# AC_Power_Management.net
KiCad netlist of a schematic drawn in Altium Designer
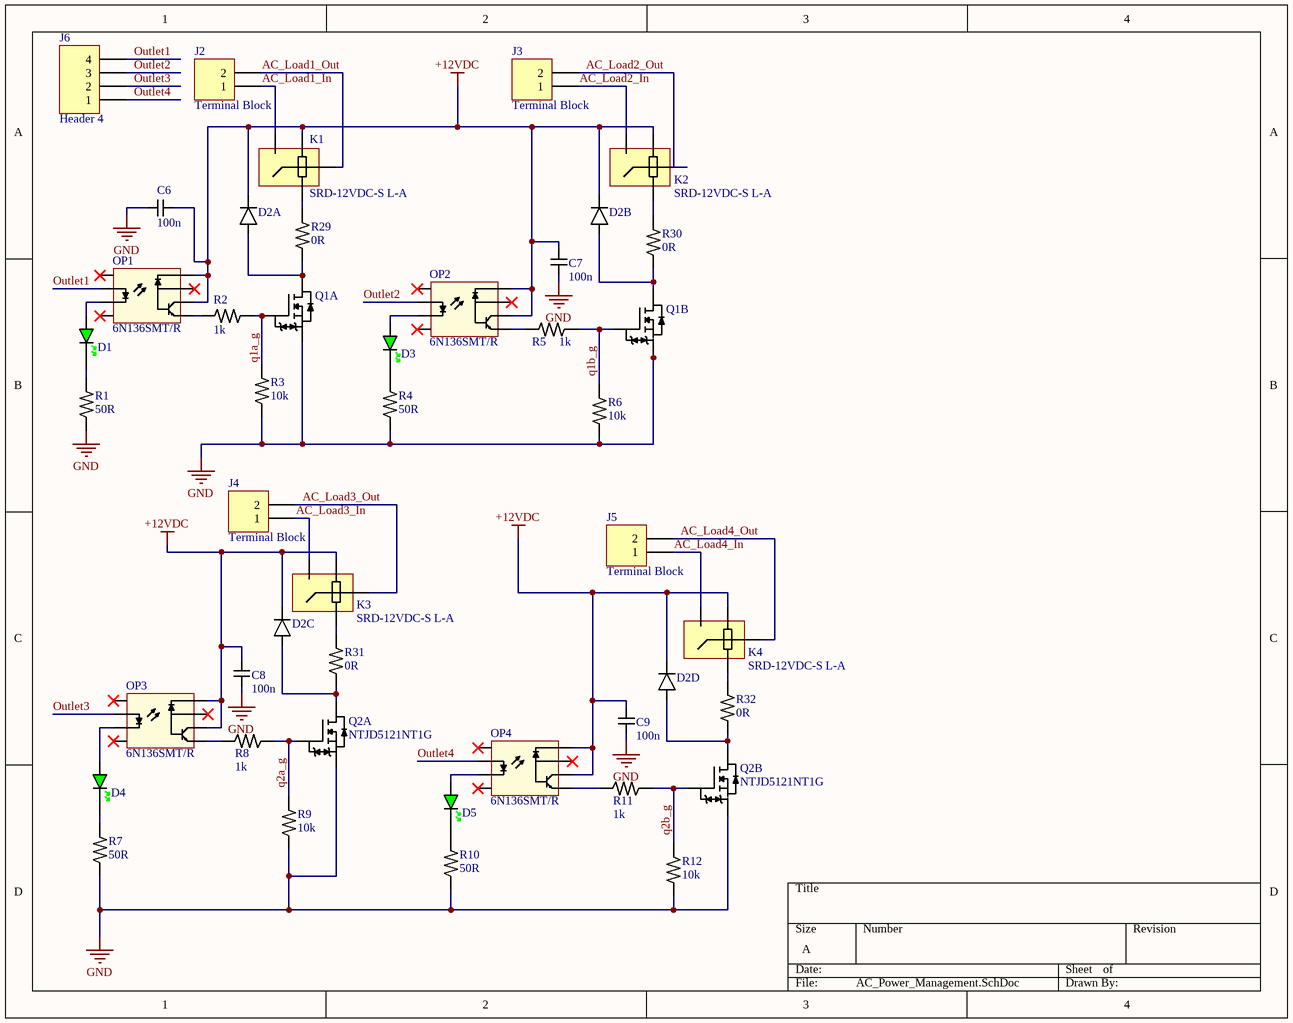
[diagram p0: AC_Power_Management.SchDoc]

(export (version "E")
  (design (tool "Eeschema 10.0.6"))
  (components
    (comp (ref "C6")
      (value "100n")
      (footprint "CAP_0402")
      (libsource (lib "PEAK_SCHEM_LIB") (part "CAP_0402"))
    )
    (comp (ref "C7")
      (value "100n")
      (footprint "CAP_0402")
      (libsource (lib "PEAK_SCHEM_LIB") (part "CAP_0402"))
    )
    (comp (ref "C8")
      (value "100n")
      (footprint "CAP_0402")
      (libsource (lib "PEAK_SCHEM_LIB") (part "CAP_0402"))
    )
    (comp (ref "C9")
      (value "100n")
      (footprint "CAP_0402")
      (libsource (lib "PEAK_SCHEM_LIB") (part "CAP_0402"))
    )
    (comp (ref "D1")
      (value "GREEN")
      (footprint "LED_0805_GREEN")
      (description "LED 0805 GREEN SMD")
      (libsource (lib "PEAK_SCHEM_LIB") (part "LED_0805_GREEN"))
    )
    (comp (ref "D2")
      (value "BAT54CDW-7-F")
      (footprint "SOT-363")
      (description "2 Pairs of Common Cathode Diodes in SOT363 Package BAT54CDW-7-F")
      (libsource (lib "PEAK_SCHEM_LIB") (part "BAT54CDW-7-F"))
    )
    (comp (ref "D3")
      (value "GREEN")
      (footprint "LED_0805_GREEN")
      (description "LED 0805 GREEN SMD")
      (libsource (lib "PEAK_SCHEM_LIB") (part "LED_0805_GREEN"))
    )
    (comp (ref "D4")
      (value "GREEN")
      (footprint "LED_0805_GREEN")
      (description "LED 0805 GREEN SMD")
      (libsource (lib "PEAK_SCHEM_LIB") (part "LED_0805_GREEN"))
    )
    (comp (ref "D5")
      (value "GREEN")
      (footprint "LED_0805_GREEN")
      (description "LED 0805 GREEN SMD")
      (libsource (lib "PEAK_SCHEM_LIB") (part "LED_0805_GREEN"))
    )
    (comp (ref "J2")
      (value "Terminal Block")
      (footprint "25-E400-02")
      (description "Header, 2-Pin")
      (fields (field (name "PUBLISHER") "Altium Limited"))
      (libsource (lib "Miscellaneous Connectors") (part "Header 2"))
    )
    (comp (ref "J3")
      (value "Terminal Block")
      (footprint "25-E400-02")
      (description "Header, 2-Pin")
      (fields (field (name "PUBLISHER") "Altium Limited"))
      (libsource (lib "Miscellaneous Connectors") (part "Header 2"))
    )
    (comp (ref "J4")
      (value "Terminal Block")
      (footprint "25-E400-02")
      (description "Header, 2-Pin")
      (fields (field (name "PUBLISHER") "Altium Limited"))
      (libsource (lib "Miscellaneous Connectors") (part "Header 2"))
    )
    (comp (ref "J5")
      (value "Terminal Block")
      (footprint "25-E400-02")
      (description "Header, 2-Pin")
      (fields (field (name "PUBLISHER") "Altium Limited"))
      (libsource (lib "Miscellaneous Connectors") (part "Header 2"))
    )
    (comp (ref "J6")
      (value "Header 4")
      (footprint "HDR1X4")
      (description "Header, 4-Pin")
      (fields (field (name "PUBLISHER") "Altium Limited"))
      (libsource (lib "Miscellaneous Connectors") (part "Header 4"))
    )
    (comp (ref "K1")
      (value "SRD-12VDC-S L-A")
      (footprint "SRD-12VDC-S L")
      (libsource (lib "PEAK_SCHEM_LIB") (part "SRD-12VDC-S L-A"))
    )
    (comp (ref "K2")
      (value "SRD-12VDC-S L-A")
      (footprint "SRD-12VDC-S L")
      (libsource (lib "PEAK_SCHEM_LIB") (part "SRD-12VDC-S L-A"))
    )
    (comp (ref "K3")
      (value "SRD-12VDC-S L-A")
      (footprint "SRD-12VDC-S L")
      (libsource (lib "PEAK_SCHEM_LIB") (part "SRD-12VDC-S L-A"))
    )
    (comp (ref "K4")
      (value "SRD-12VDC-S L-A")
      (footprint "SRD-12VDC-S L")
      (libsource (lib "PEAK_SCHEM_LIB") (part "SRD-12VDC-S L-A"))
    )
    (comp (ref "OP1")
      (value "6N136SMT/R")
      (footprint "SOP-8-2.54mm")
      (description "Optocouplers SMD-8 RoHS. SOP-8-2.54mm Package")
      (libsource (lib "PEAK_SCHEM_LIB") (part "6N136SMT/R"))
    )
    (comp (ref "OP2")
      (value "6N136SMT/R")
      (footprint "SOP-8-2.54mm")
      (description "Optocouplers SMD-8 RoHS. SOP-8-2.54mm Package")
      (libsource (lib "PEAK_SCHEM_LIB") (part "6N136SMT/R"))
    )
    (comp (ref "OP3")
      (value "6N136SMT/R")
      (footprint "SOP-8-2.54mm")
      (description "Optocouplers SMD-8 RoHS. SOP-8-2.54mm Package")
      (libsource (lib "PEAK_SCHEM_LIB") (part "6N136SMT/R"))
    )
    (comp (ref "OP4")
      (value "6N136SMT/R")
      (footprint "SOP-8-2.54mm")
      (description "Optocouplers SMD-8 RoHS. SOP-8-2.54mm Package")
      (libsource (lib "PEAK_SCHEM_LIB") (part "6N136SMT/R"))
    )
    (comp (ref "Q1")
      (value "NTJD5121NT1G")
      (footprint "SOT-363")
      (description "2 NMOSFETs SOT-363")
      (libsource (lib "PEAK_SCHEM_LIB") (part "NTJD5121NT1G"))
    )
    (comp (ref "Q2")
      (value "NTJD5121NT1G")
      (footprint "SOT-363")
      (description "2 NMOSFETs SOT-363")
      (libsource (lib "PEAK_SCHEM_LIB") (part "NTJD5121NT1G"))
    )
    (comp (ref "R1")
      (value "50R")
      (footprint "RES_0402")
      (description "Resistor SMD 0402 (0.0625W)")
      (libsource (lib "PEAK_SCHEM_LIB") (part "RES_0402"))
    )
    (comp (ref "R2")
      (value "1k")
      (footprint "RES_0402")
      (description "Resistor SMD 0402 (0.0625W)")
      (libsource (lib "PEAK_SCHEM_LIB") (part "RES_0402"))
    )
    (comp (ref "R3")
      (value "10k")
      (footprint "RES_0402")
      (description "Resistor SMD 0402 (0.0625W)")
      (libsource (lib "PEAK_SCHEM_LIB") (part "RES_0402"))
    )
    (comp (ref "R4")
      (value "50R")
      (footprint "RES_0402")
      (description "Resistor SMD 0402 (0.0625W)")
      (libsource (lib "PEAK_SCHEM_LIB") (part "RES_0402"))
    )
    (comp (ref "R5")
      (value "1k")
      (footprint "RES_0402")
      (description "Resistor SMD 0402 (0.0625W)")
      (libsource (lib "PEAK_SCHEM_LIB") (part "RES_0402"))
    )
    (comp (ref "R6")
      (value "10k")
      (footprint "RES_0402")
      (description "Resistor SMD 0402 (0.0625W)")
      (libsource (lib "PEAK_SCHEM_LIB") (part "RES_0402"))
    )
    (comp (ref "R7")
      (value "50R")
      (footprint "RES_0402")
      (description "Resistor SMD 0402 (0.0625W)")
      (libsource (lib "PEAK_SCHEM_LIB") (part "RES_0402"))
    )
    (comp (ref "R8")
      (value "1k")
      (footprint "RES_0402")
      (description "Resistor SMD 0402 (0.0625W)")
      (libsource (lib "PEAK_SCHEM_LIB") (part "RES_0402"))
    )
    (comp (ref "R9")
      (value "10k")
      (footprint "RES_0402")
      (description "Resistor SMD 0402 (0.0625W)")
      (libsource (lib "PEAK_SCHEM_LIB") (part "RES_0402"))
    )
    (comp (ref "R10")
      (value "50R")
      (footprint "RES_0402")
      (description "Resistor SMD 0402 (0.0625W)")
      (libsource (lib "PEAK_SCHEM_LIB") (part "RES_0402"))
    )
    (comp (ref "R11")
      (value "1k")
      (footprint "RES_0402")
      (description "Resistor SMD 0402 (0.0625W)")
      (libsource (lib "PEAK_SCHEM_LIB") (part "RES_0402"))
    )
    (comp (ref "R12")
      (value "10k")
      (footprint "RES_0402")
      (description "Resistor SMD 0402 (0.0625W)")
      (libsource (lib "PEAK_SCHEM_LIB") (part "RES_0402"))
    )
    (comp (ref "R29")
      (value "0R")
      (footprint "RES_0402")
      (description "Resistor SMD 0402 (0.0625W)")
      (libsource (lib "PEAK_SCHEM_LIB") (part "RES_0402"))
    )
    (comp (ref "R30")
      (value "0R")
      (footprint "RES_0402")
      (description "Resistor SMD 0402 (0.0625W)")
      (libsource (lib "PEAK_SCHEM_LIB") (part "RES_0402"))
    )
    (comp (ref "R31")
      (value "0R")
      (footprint "RES_0402")
      (description "Resistor SMD 0402 (0.0625W)")
      (libsource (lib "PEAK_SCHEM_LIB") (part "RES_0402"))
    )
    (comp (ref "R32")
      (value "0R")
      (footprint "RES_0402")
      (description "Resistor SMD 0402 (0.0625W)")
      (libsource (lib "PEAK_SCHEM_LIB") (part "RES_0402"))
    )
  )
  (nets
    (net (code "1") (name "+12VDC") (class "Default")
      (node (ref "C6") (pin "1") (pinfunction "1_1") (pintype "passive"))
      (node (ref "C7") (pin "1") (pinfunction "1_1") (pintype "passive"))
      (node (ref "C8") (pin "1") (pinfunction "1_1") (pintype "passive"))
      (node (ref "C9") (pin "1") (pinfunction "1_1") (pintype "passive"))
      (node (ref "D2") (pin "1") (pinfunction "C1_1") (pintype "passive"))
      (node (ref "D2") (pin "4") (pinfunction "C2_4") (pintype "passive"))
      (node (ref "K1") (pin "4") (pinfunction "4_4") (pintype "passive"))
      (node (ref "K2") (pin "4") (pinfunction "4_4") (pintype "passive"))
      (node (ref "K3") (pin "4") (pinfunction "4_4") (pintype "passive"))
      (node (ref "K4") (pin "4") (pinfunction "4_4") (pintype "passive"))
      (node (ref "OP1") (pin "6") (pinfunction "Vo_6") (pintype "passive"))
      (node (ref "OP1") (pin "8") (pinfunction "Vcc_8") (pintype "passive"))
      (node (ref "OP2") (pin "6") (pinfunction "Vo_6") (pintype "passive"))
      (node (ref "OP2") (pin "8") (pinfunction "Vcc_8") (pintype "passive"))
      (node (ref "OP3") (pin "6") (pinfunction "Vo_6") (pintype "passive"))
      (node (ref "OP3") (pin "8") (pinfunction "Vcc_8") (pintype "passive"))
      (node (ref "OP4") (pin "6") (pinfunction "Vo_6") (pintype "passive"))
      (node (ref "OP4") (pin "8") (pinfunction "Vcc_8") (pintype "passive"))
    )
    (net (code "2") (name "/AC_Load1_In") (class "Default")
      (node (ref "J2") (pin "1") (pinfunction "1_1") (pintype "passive"))
      (node (ref "K1") (pin "1") (pinfunction "1_1") (pintype "passive"))
    )
    (net (code "3") (name "/AC_Load1_Out") (class "Default")
      (node (ref "J2") (pin "2") (pinfunction "2_2") (pintype "passive"))
      (node (ref "K1") (pin "3") (pinfunction "3_3") (pintype "passive"))
    )
    (net (code "4") (name "/AC_Load2_In") (class "Default")
      (node (ref "J3") (pin "1") (pinfunction "1_1") (pintype "passive"))
      (node (ref "K2") (pin "1") (pinfunction "1_1") (pintype "passive"))
    )
    (net (code "5") (name "/AC_Load2_Out") (class "Default")
      (node (ref "J3") (pin "2") (pinfunction "2_2") (pintype "passive"))
      (node (ref "K2") (pin "3") (pinfunction "3_3") (pintype "passive"))
    )
    (net (code "6") (name "/AC_Load3_In") (class "Default")
      (node (ref "J4") (pin "1") (pinfunction "1_1") (pintype "passive"))
      (node (ref "K3") (pin "1") (pinfunction "1_1") (pintype "passive"))
    )
    (net (code "7") (name "/AC_Load3_Out") (class "Default")
      (node (ref "J4") (pin "2") (pinfunction "2_2") (pintype "passive"))
      (node (ref "K3") (pin "3") (pinfunction "3_3") (pintype "passive"))
    )
    (net (code "8") (name "/AC_Load4_In") (class "Default")
      (node (ref "J5") (pin "1") (pinfunction "1_1") (pintype "passive"))
      (node (ref "K4") (pin "1") (pinfunction "1_1") (pintype "passive"))
    )
    (net (code "9") (name "/AC_Load4_Out") (class "Default")
      (node (ref "J5") (pin "2") (pinfunction "2_2") (pintype "passive"))
      (node (ref "K4") (pin "3") (pinfunction "3_3") (pintype "passive"))
    )
    (net (code "10") (name "/Outlet1") (class "Default")
      (node (ref "J6") (pin "4") (pinfunction "4_4") (pintype "passive"))
      (node (ref "OP1") (pin "2") (pinfunction "A_2") (pintype "passive"))
    )
    (net (code "11") (name "/Outlet2") (class "Default")
      (node (ref "J6") (pin "3") (pinfunction "3_3") (pintype "passive"))
      (node (ref "OP2") (pin "2") (pinfunction "A_2") (pintype "passive"))
    )
    (net (code "12") (name "/Outlet3") (class "Default")
      (node (ref "J6") (pin "2") (pinfunction "2_2") (pintype "passive"))
      (node (ref "OP3") (pin "2") (pinfunction "A_2") (pintype "passive"))
    )
    (net (code "13") (name "/Outlet4") (class "Default")
      (node (ref "J6") (pin "1") (pinfunction "1_1") (pintype "passive"))
      (node (ref "OP4") (pin "2") (pinfunction "A_2") (pintype "passive"))
    )
    (net (code "14") (name "/q1a_g") (class "Default")
      (node (ref "Q1") (pin "2") (pinfunction "G1_2") (pintype "passive"))
      (node (ref "R2") (pin "2") (pinfunction "2_2") (pintype "passive"))
      (node (ref "R3") (pin "2") (pinfunction "2_2") (pintype "passive"))
    )
    (net (code "15") (name "/q1b_g") (class "Default")
      (node (ref "Q1") (pin "5") (pinfunction "G2_5") (pintype "passive"))
      (node (ref "R5") (pin "2") (pinfunction "2_2") (pintype "passive"))
      (node (ref "R6") (pin "2") (pinfunction "2_2") (pintype "passive"))
    )
    (net (code "16") (name "/q2a_g") (class "Default")
      (node (ref "Q2") (pin "2") (pinfunction "G1_2") (pintype "passive"))
      (node (ref "R8") (pin "2") (pinfunction "2_2") (pintype "passive"))
      (node (ref "R9") (pin "2") (pinfunction "2_2") (pintype "passive"))
    )
    (net (code "17") (name "/q2b_g") (class "Default")
      (node (ref "Q2") (pin "5") (pinfunction "G2_5") (pintype "passive"))
      (node (ref "R11") (pin "2") (pinfunction "2_2") (pintype "passive"))
      (node (ref "R12") (pin "2") (pinfunction "2_2") (pintype "passive"))
    )
    (net (code "18") (name "GND") (class "Default")
      (node (ref "C6") (pin "2") (pinfunction "2_2") (pintype "passive"))
      (node (ref "C7") (pin "2") (pinfunction "2_2") (pintype "passive"))
      (node (ref "C8") (pin "2") (pinfunction "2_2") (pintype "passive"))
      (node (ref "C9") (pin "2") (pinfunction "2_2") (pintype "passive"))
      (node (ref "Q1") (pin "3") (pinfunction "S1_3") (pintype "passive"))
      (node (ref "Q1") (pin "6") (pinfunction "S2_6") (pintype "passive"))
      (node (ref "Q2") (pin "3") (pinfunction "S1_3") (pintype "passive"))
      (node (ref "Q2") (pin "6") (pinfunction "S2_6") (pintype "passive"))
      (node (ref "R1") (pin "1") (pinfunction "1_1") (pintype "passive"))
      (node (ref "R10") (pin "1") (pinfunction "1_1") (pintype "passive"))
      (node (ref "R12") (pin "1") (pinfunction "1_1") (pintype "passive"))
      (node (ref "R3") (pin "1") (pinfunction "1_1") (pintype "passive"))
      (node (ref "R4") (pin "1") (pinfunction "1_1") (pintype "passive"))
      (node (ref "R6") (pin "1") (pinfunction "1_1") (pintype "passive"))
      (node (ref "R7") (pin "1") (pinfunction "1_1") (pintype "passive"))
      (node (ref "R9") (pin "1") (pinfunction "1_1") (pintype "passive"))
    )
    (net (code "19") (name "Net-(D1-PadK)") (class "Default")
      (node (ref "D1") (pin "K") (pinfunction "K_K") (pintype "passive"))
      (node (ref "R1") (pin "2") (pinfunction "2_2") (pintype "passive"))
    )
    (net (code "20") (name "Net-(D2A-A1_1)") (class "Default")
      (node (ref "D2") (pin "5") (pinfunction "A1_1_5") (pintype "passive"))
      (node (ref "Q1") (pin "1") (pinfunction "D1_1") (pintype "passive"))
      (node (ref "R29") (pin "1") (pinfunction "1_1") (pintype "passive"))
    )
    (net (code "21") (name "Net-(D2B-A1_2)") (class "Default")
      (node (ref "D2") (pin "6") (pinfunction "A1_2_6") (pintype "passive"))
      (node (ref "Q1") (pin "4") (pinfunction "D2_4") (pintype "passive"))
      (node (ref "R30") (pin "1") (pinfunction "1_1") (pintype "passive"))
    )
    (net (code "22") (name "Net-(D2C-A2_1)") (class "Default")
      (node (ref "D2") (pin "2") (pinfunction "A2_1_2") (pintype "passive"))
      (node (ref "Q2") (pin "1") (pinfunction "D1_1") (pintype "passive"))
      (node (ref "R31") (pin "1") (pinfunction "1_1") (pintype "passive"))
    )
    (net (code "23") (name "Net-(D2D-A2_2)") (class "Default")
      (node (ref "D2") (pin "3") (pinfunction "A2_2_3") (pintype "passive"))
      (node (ref "Q2") (pin "4") (pinfunction "D2_4") (pintype "passive"))
      (node (ref "R32") (pin "1") (pinfunction "1_1") (pintype "passive"))
    )
    (net (code "24") (name "Net-(D3-PadK)") (class "Default")
      (node (ref "D3") (pin "K") (pinfunction "K_K") (pintype "passive"))
      (node (ref "R4") (pin "2") (pinfunction "2_2") (pintype "passive"))
    )
    (net (code "25") (name "Net-(D4-PadK)") (class "Default")
      (node (ref "D4") (pin "K") (pinfunction "K_K") (pintype "passive"))
      (node (ref "R7") (pin "2") (pinfunction "2_2") (pintype "passive"))
    )
    (net (code "26") (name "Net-(D5-PadK)") (class "Default")
      (node (ref "D5") (pin "K") (pinfunction "K_K") (pintype "passive"))
      (node (ref "R10") (pin "2") (pinfunction "2_2") (pintype "passive"))
    )
    (net (code "27") (name "Net-(K1-Pad2)") (class "Default")
      (node (ref "K1") (pin "2") (pinfunction "2_2") (pintype "passive"))
      (node (ref "R29") (pin "2") (pinfunction "2_2") (pintype "passive"))
    )
    (net (code "28") (name "Net-(K2-Pad2)") (class "Default")
      (node (ref "K2") (pin "2") (pinfunction "2_2") (pintype "passive"))
      (node (ref "R30") (pin "2") (pinfunction "2_2") (pintype "passive"))
    )
    (net (code "29") (name "Net-(K3-Pad2)") (class "Default")
      (node (ref "K3") (pin "2") (pinfunction "2_2") (pintype "passive"))
      (node (ref "R31") (pin "2") (pinfunction "2_2") (pintype "passive"))
    )
    (net (code "30") (name "Net-(K4-Pad2)") (class "Default")
      (node (ref "K4") (pin "2") (pinfunction "2_2") (pintype "passive"))
      (node (ref "R32") (pin "2") (pinfunction "2_2") (pintype "passive"))
    )
    (net (code "31") (name "Net-(OP1-C)") (class "Default")
      (node (ref "D1") (pin "A") (pinfunction "A_A") (pintype "passive"))
      (node (ref "OP1") (pin "3") (pinfunction "C_3") (pintype "passive"))
    )
    (net (code "32") (name "Net-(OP1-GND)") (class "Default")
      (node (ref "OP1") (pin "5") (pinfunction "GND_5") (pintype "passive"))
      (node (ref "R2") (pin "1") (pinfunction "1_1") (pintype "passive"))
    )
    (net (code "33") (name "Net-(OP2-C)") (class "Default")
      (node (ref "D3") (pin "A") (pinfunction "A_A") (pintype "passive"))
      (node (ref "OP2") (pin "3") (pinfunction "C_3") (pintype "passive"))
    )
    (net (code "34") (name "Net-(OP2-GND)") (class "Default")
      (node (ref "OP2") (pin "5") (pinfunction "GND_5") (pintype "passive"))
      (node (ref "R5") (pin "1") (pinfunction "1_1") (pintype "passive"))
    )
    (net (code "35") (name "Net-(OP3-C)") (class "Default")
      (node (ref "D4") (pin "A") (pinfunction "A_A") (pintype "passive"))
      (node (ref "OP3") (pin "3") (pinfunction "C_3") (pintype "passive"))
    )
    (net (code "36") (name "Net-(OP3-GND)") (class "Default")
      (node (ref "OP3") (pin "5") (pinfunction "GND_5") (pintype "passive"))
      (node (ref "R8") (pin "1") (pinfunction "1_1") (pintype "passive"))
    )
    (net (code "37") (name "Net-(OP4-C)") (class "Default")
      (node (ref "D5") (pin "A") (pinfunction "A_A") (pintype "passive"))
      (node (ref "OP4") (pin "3") (pinfunction "C_3") (pintype "passive"))
    )
    (net (code "38") (name "Net-(OP4-GND)") (class "Default")
      (node (ref "OP4") (pin "5") (pinfunction "GND_5") (pintype "passive"))
      (node (ref "R11") (pin "1") (pinfunction "1_1") (pintype "passive"))
    )
    (net (code "39") (name "unconnected-(OP1-NC-Pad1)") (class "Default")
      (node (ref "OP1") (pin "1") (pinfunction "NC_1") (pintype "passive+no_connect"))
    )
    (net (code "40") (name "unconnected-(OP1-NC-Pad4)") (class "Default")
      (node (ref "OP1") (pin "4") (pinfunction "NC_4") (pintype "passive+no_connect"))
    )
    (net (code "41") (name "unconnected-(OP1-Vb-Pad7)") (class "Default")
      (node (ref "OP1") (pin "7") (pinfunction "Vb_7") (pintype "passive+no_connect"))
    )
    (net (code "42") (name "unconnected-(OP2-NC-Pad1)") (class "Default")
      (node (ref "OP2") (pin "1") (pinfunction "NC_1") (pintype "passive+no_connect"))
    )
    (net (code "43") (name "unconnected-(OP2-NC-Pad4)") (class "Default")
      (node (ref "OP2") (pin "4") (pinfunction "NC_4") (pintype "passive+no_connect"))
    )
    (net (code "44") (name "unconnected-(OP2-Vb-Pad7)") (class "Default")
      (node (ref "OP2") (pin "7") (pinfunction "Vb_7") (pintype "passive+no_connect"))
    )
    (net (code "45") (name "unconnected-(OP3-NC-Pad1)") (class "Default")
      (node (ref "OP3") (pin "1") (pinfunction "NC_1") (pintype "passive+no_connect"))
    )
    (net (code "46") (name "unconnected-(OP3-NC-Pad4)") (class "Default")
      (node (ref "OP3") (pin "4") (pinfunction "NC_4") (pintype "passive+no_connect"))
    )
    (net (code "47") (name "unconnected-(OP3-Vb-Pad7)") (class "Default")
      (node (ref "OP3") (pin "7") (pinfunction "Vb_7") (pintype "passive+no_connect"))
    )
    (net (code "48") (name "unconnected-(OP4-NC-Pad1)") (class "Default")
      (node (ref "OP4") (pin "1") (pinfunction "NC_1") (pintype "passive+no_connect"))
    )
    (net (code "49") (name "unconnected-(OP4-NC-Pad4)") (class "Default")
      (node (ref "OP4") (pin "4") (pinfunction "NC_4") (pintype "passive+no_connect"))
    )
    (net (code "50") (name "unconnected-(OP4-Vb-Pad7)") (class "Default")
      (node (ref "OP4") (pin "7") (pinfunction "Vb_7") (pintype "passive+no_connect"))
    )
  )
)
